# SCB_XTR.net
KiCad netlist of a schematic drawn in Altium Designer
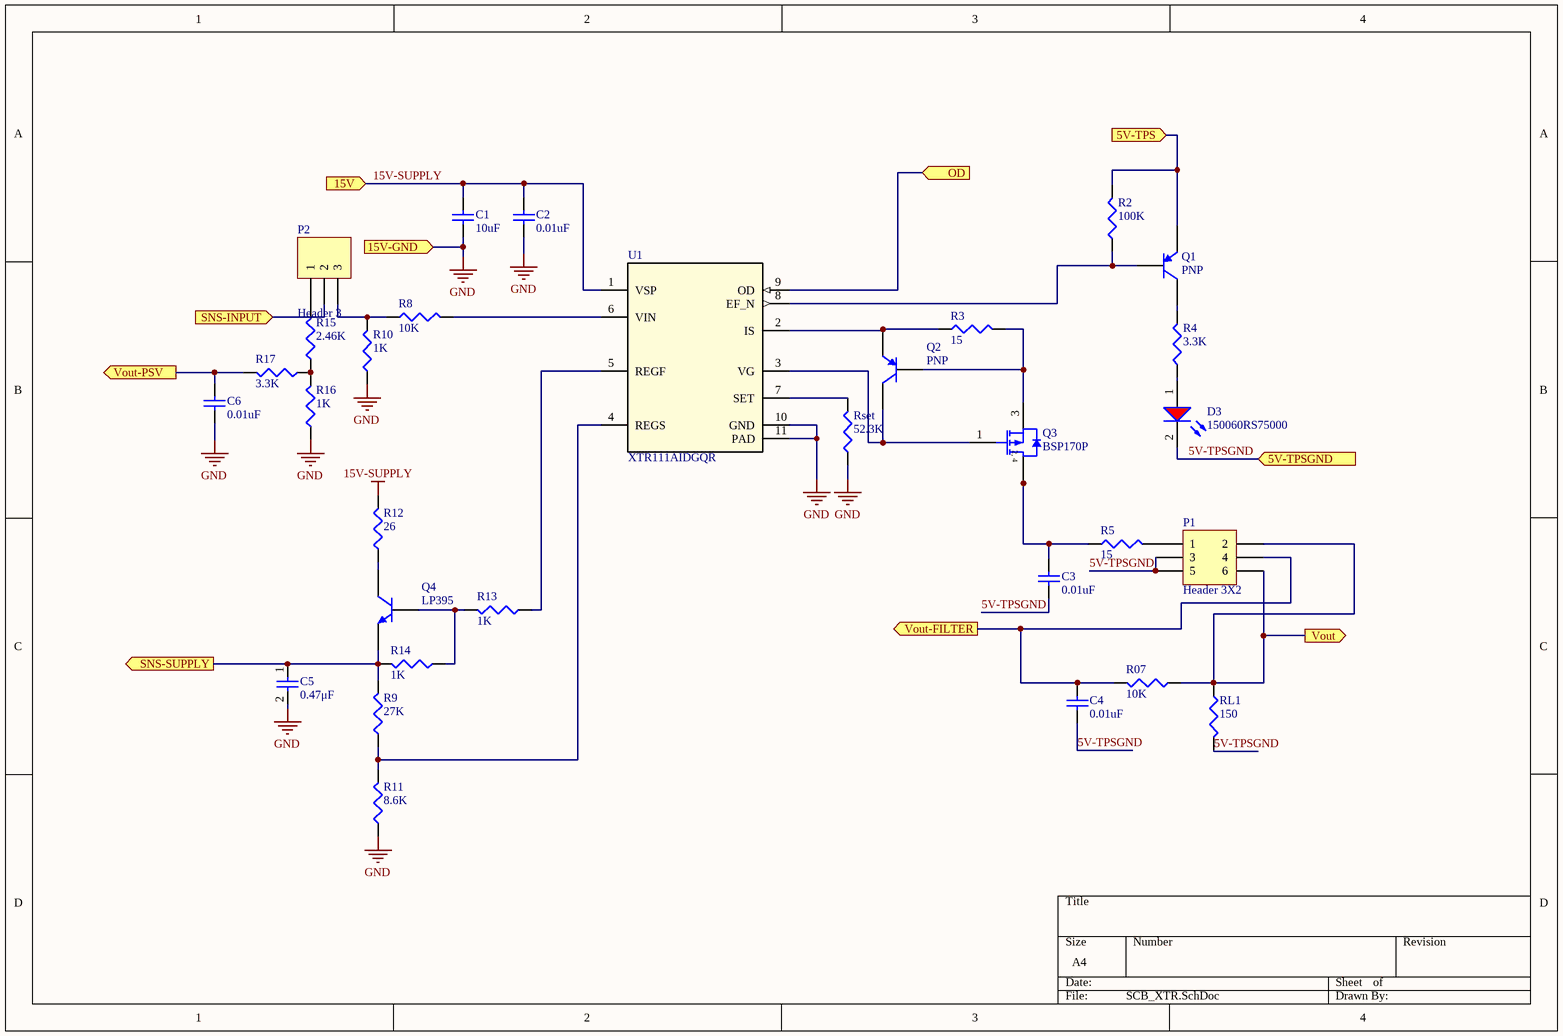
[diagram p0: SCB_XTR.SchDoc]

(export (version "E")
  (design (tool "Eeschema 10.0.6"))
  (components
    (comp (ref "C1")
      (value "10uF")
      (footprint "RAD-0.3")
      (description "Capacitor")
      (fields (field (name "PUBLISHER") "Altium Limited"))
      (libsource (lib "Miscellaneous Devices") (part "Cap"))
    )
    (comp (ref "C2")
      (value "0.01uF")
      (footprint "1608[0603]")
      (description "Capacitor (Semiconductor SIM Model)")
      (fields (field (name "PUBLISHER") "Altium Limited"))
      (libsource (lib "Miscellaneous Devices") (part "Cap Semi"))
    )
    (comp (ref "C3")
      (value "0.01uF")
      (footprint "1608[0603]")
      (description "Capacitor (Semiconductor SIM Model)")
      (fields (field (name "PUBLISHER") "Altium Limited"))
      (libsource (lib "Miscellaneous Devices") (part "Cap Semi"))
    )
    (comp (ref "C4")
      (value "0.01uF")
      (footprint "1608[0603]")
      (description "Capacitor (Semiconductor SIM Model)")
      (fields (field (name "PUBLISHER") "Altium Limited"))
      (libsource (lib "Miscellaneous Devices") (part "Cap Semi"))
    )
    (comp (ref "C5")
      (value "0.47μF")
      (footprint "WCAP-CSGP 0805, H=1.25mm")
      (description "CAP CER 1UF 50V 10% X5R 0805")
      (fields
        (field (name "MANUFACTURER") "TDK")
        (field (name "PARTNO") "CGA4J3X5R1H105K125AB")
        (field (name "CREATED BY") "Saurabh")
      )
      (libsource (lib "WCAP-CSGP_rev15b") (part "WCAP-CSGP 0805, 885012207026"))
    )
    (comp (ref "C6")
      (value "0.01uF")
      (footprint "1608[0603]")
      (description "Capacitor (Semiconductor SIM Model)")
      (fields (field (name "PUBLISHER") "Altium Limited"))
      (libsource (lib "Miscellaneous Devices") (part "Cap Semi"))
    )
    (comp (ref "D3")
      (value "150060RS75000")
      (footprint "LED_0603_Red")
      (description "SMD mono-color Chip LED, WL-SMCW, Red")
      (fields
        (field (name "MANUFACTURER") "W黵th Elektronik eiSos GmbH")
        (field (name "CREATED BY") "Christin Otto")
      )
      (libsource (lib "WL-SMCW_rev15b") (part "WL-SMCW 0603  150060RS75000"))
    )
    (comp (ref "P1")
      (value "Header 3X2")
      (footprint "HDR2X3")
      (description "Header, 3-Pin, Dual row")
      (fields (field (name "PUBLISHER") "Altium Limited"))
      (libsource (lib "Miscellaneous Connectors") (part "Header 3X2"))
    )
    (comp (ref "P2")
      (value "Header 3")
      (footprint "HDR1X3")
      (description "Header, 3-Pin")
      (fields (field (name "PUBLISHER") "Altium Limited"))
      (libsource (lib "Miscellaneous Connectors") (part "Header 3"))
    )
    (comp (ref "Q1")
      (value "PNP")
      (footprint "SOT-23B_N")
      (description "PNP Bipolar Transistor")
      (fields (field (name "PUBLISHER") "Altium Limited"))
      (libsource (lib "Miscellaneous Devices") (part "PNP"))
    )
    (comp (ref "Q2")
      (value "PNP")
      (footprint "SOT-23B_N")
      (description "PNP Bipolar Transistor")
      (fields (field (name "PUBLISHER") "Altium Limited"))
      (libsource (lib "Miscellaneous Devices") (part "PNP"))
    )
    (comp (ref "Q3")
      (value "BSP170P")
      (footprint "INF-PG-SOT223_SC-73_M")
      (fields (field (name "MANUFACTURER") "Infineon"))
      (libsource (lib "BSP170P") (part "BSP170P"))
    )
    (comp (ref "Q4")
      (value "LP395")
      (footprint "TO-92A")
      (description "NPN General Purpose Amplifier")
      (fields (field (name "PUBLISHER") "Altium Limited"))
      (libsource (lib "Miscellaneous Devices") (part "2N3904"))
    )
    (comp (ref "R2")
      (value "100K")
      (footprint "J1-0603")
      (description "Resistor")
      (fields (field (name "PUBLISHER") "Altium Limited"))
      (libsource (lib "Miscellaneous Devices") (part "Res3"))
    )
    (comp (ref "R3")
      (value "15")
      (footprint "J1-0603")
      (description "Resistor")
      (fields (field (name "PUBLISHER") "Altium Limited"))
      (libsource (lib "Miscellaneous Devices") (part "Res3"))
    )
    (comp (ref "R4")
      (value "3.3K")
      (footprint "J1-0603")
      (description "Resistor")
      (fields (field (name "PUBLISHER") "Altium Limited"))
      (libsource (lib "Miscellaneous Devices") (part "Res3"))
    )
    (comp (ref "R5")
      (value "15")
      (footprint "J1-0603")
      (description "Resistor")
      (fields (field (name "PUBLISHER") "Altium Limited"))
      (libsource (lib "Miscellaneous Devices") (part "Res3"))
    )
    (comp (ref "R07")
      (value "10K")
      (footprint "J1-0603")
      (description "Resistor")
      (fields (field (name "PUBLISHER") "Altium Limited"))
      (libsource (lib "Miscellaneous Devices") (part "Res3"))
    )
    (comp (ref "R8")
      (value "10K")
      (footprint "J1-0603")
      (description "Resistor")
      (fields (field (name "PUBLISHER") "Altium Limited"))
      (libsource (lib "Miscellaneous Devices") (part "Res3"))
    )
    (comp (ref "R9")
      (value "27K")
      (footprint "J1-0603")
      (description "Resistor")
      (fields (field (name "PUBLISHER") "Altium Limited"))
      (libsource (lib "Miscellaneous Devices") (part "Res3"))
    )
    (comp (ref "R10")
      (value "1K")
      (footprint "J1-0603")
      (description "Resistor")
      (fields (field (name "PUBLISHER") "Altium Limited"))
      (libsource (lib "Miscellaneous Devices") (part "Res3"))
    )
    (comp (ref "R11")
      (value "8.6K")
      (footprint "J1-0603")
      (description "Resistor")
      (fields (field (name "PUBLISHER") "Altium Limited"))
      (libsource (lib "Miscellaneous Devices") (part "Res3"))
    )
    (comp (ref "R12")
      (value "26")
      (footprint "J1-0603")
      (description "Resistor")
      (fields (field (name "PUBLISHER") "Altium Limited"))
      (libsource (lib "Miscellaneous Devices") (part "Res3"))
    )
    (comp (ref "R13")
      (value "1K")
      (footprint "J1-0603")
      (description "Resistor")
      (fields (field (name "PUBLISHER") "Altium Limited"))
      (libsource (lib "Miscellaneous Devices") (part "Res3"))
    )
    (comp (ref "R14")
      (value "1K")
      (footprint "J1-0603")
      (description "Resistor")
      (fields (field (name "PUBLISHER") "Altium Limited"))
      (libsource (lib "Miscellaneous Devices") (part "Res3"))
    )
    (comp (ref "R15")
      (value "2.46K")
      (footprint "J1-0603")
      (description "Resistor")
      (fields (field (name "PUBLISHER") "Altium Limited"))
      (libsource (lib "Miscellaneous Devices") (part "Res3"))
    )
    (comp (ref "R16")
      (value "1K")
      (footprint "J1-0603")
      (description "Resistor")
      (fields (field (name "PUBLISHER") "Altium Limited"))
      (libsource (lib "Miscellaneous Devices") (part "Res3"))
    )
    (comp (ref "R17")
      (value "3.3K")
      (footprint "J1-0603")
      (description "Resistor")
      (fields (field (name "PUBLISHER") "Altium Limited"))
      (libsource (lib "Miscellaneous Devices") (part "Res3"))
    )
    (comp (ref "RL1")
      (value "150")
      (footprint "J1-0603")
      (description "Resistor")
      (fields (field (name "PUBLISHER") "Altium Limited"))
      (libsource (lib "Miscellaneous Devices") (part "Res3"))
    )
    (comp (ref "Rset")
      (value "52.3K")
      (footprint "RESC2012M")
      (description "Resistor")
      (fields (field (name "PUBLISHER") "Altium Limited"))
      (libsource (lib "Miscellaneous Devices") (part "Res3"))
    )
    (comp (ref "U1")
      (value "XTR111AIDGQR")
      (footprint "DGQ0010D_NV_N")
      (description "Imported")
      (fields (field (name "PARTNUMBER") "XTR111AIDGQT") (field (name "MANUFACTURER") "Texas Instruments"))
      (libsource (lib "2016-09-29_20-01-59") (part "XTR111AIDGQR"))
    )
  )
  (nets
    (net (code "1") (name "/5V-TPS") (class "Default")
      (node (ref "Q1") (pin "3") (pinfunction "E_3") (pintype "passive"))
      (node (ref "R2") (pin "2") (pinfunction "2_2") (pintype "passive"))
    )
    (net (code "2") (name "/5V-TPSGND") (class "Default")
      (node (ref "C3") (pin "1") (pinfunction "1_1") (pintype "passive"))
      (node (ref "C4") (pin "1") (pinfunction "1_1") (pintype "passive"))
      (node (ref "D3") (pin "2") (pinfunction "C_2") (pintype "passive"))
      (node (ref "P1") (pin "3") (pinfunction "3_3") (pintype "passive"))
      (node (ref "P1") (pin "5") (pinfunction "5_5") (pintype "passive"))
      (node (ref "RL1") (pin "2") (pinfunction "2_2") (pintype "passive"))
    )
    (net (code "3") (name "/OD") (class "Default")
      (node (ref "U1") (pin "9") (pinfunction "OD_9") (pintype "input"))
    )
    (net (code "4") (name "/SNS-INPUT") (class "Default")
      (node (ref "P2") (pin "2") (pinfunction "2_2") (pintype "passive"))
    )
    (net (code "5") (name "/SNS-SUPPLY") (class "Default")
      (node (ref "C5") (pin "1") (pinfunction "1_1") (pintype "passive"))
      (node (ref "Q4") (pin "1") (pinfunction "E_1") (pintype "passive"))
      (node (ref "R14") (pin "2") (pinfunction "2_2") (pintype "passive"))
      (node (ref "R9") (pin "2") (pinfunction "2_2") (pintype "passive"))
    )
    (net (code "6") (name "/Vout") (class "Default")
      (node (ref "P1") (pin "2") (pinfunction "2_2") (pintype "passive"))
      (node (ref "P1") (pin "6") (pinfunction "6_6") (pintype "passive"))
      (node (ref "R07") (pin "1") (pinfunction "1_1") (pintype "passive"))
      (node (ref "RL1") (pin "1") (pinfunction "1_1") (pintype "passive"))
    )
    (net (code "7") (name "/Vout-FILTER") (class "Default")
      (node (ref "C4") (pin "2") (pinfunction "2_2") (pintype "passive"))
      (node (ref "P1") (pin "4") (pinfunction "4_4") (pintype "passive"))
      (node (ref "R07") (pin "2") (pinfunction "2_2") (pintype "passive"))
    )
    (net (code "8") (name "/Vout-PSV") (class "Default")
      (node (ref "C6") (pin "2") (pinfunction "2_2") (pintype "passive"))
      (node (ref "R17") (pin "2") (pinfunction "2_2") (pintype "passive"))
    )
    (net (code "9") (name "15V-SUPPLY") (class "Default")
      (node (ref "C1") (pin "2") (pinfunction "2_2") (pintype "passive"))
      (node (ref "C2") (pin "2") (pinfunction "2_2") (pintype "passive"))
      (node (ref "R12") (pin "2") (pinfunction "2_2") (pintype "passive"))
      (node (ref "U1") (pin "1") (pinfunction "VSP_1") (pintype "power_in"))
    )
    (net (code "10") (name "GND") (class "Default")
      (node (ref "C1") (pin "1") (pinfunction "1_1") (pintype "passive"))
      (node (ref "C2") (pin "1") (pinfunction "1_1") (pintype "passive"))
      (node (ref "C5") (pin "2") (pinfunction "2_2") (pintype "passive"))
      (node (ref "C6") (pin "1") (pinfunction "1_1") (pintype "passive"))
      (node (ref "R10") (pin "1") (pinfunction "1_1") (pintype "passive"))
      (node (ref "R11") (pin "1") (pinfunction "1_1") (pintype "passive"))
      (node (ref "R16") (pin "1") (pinfunction "1_1") (pintype "passive"))
      (node (ref "Rset") (pin "1") (pinfunction "1_1") (pintype "passive"))
      (node (ref "U1") (pin "10") (pinfunction "GND_10") (pintype "power_in"))
      (node (ref "U1") (pin "11") (pinfunction "PAD_11") (pintype "power_in"))
    )
    (net (code "11") (name "Net-(C3-Pad2)") (class "Default")
      (node (ref "C3") (pin "2") (pinfunction "2_2") (pintype "passive"))
      (node (ref "Q3") (pin "2") (pinfunction "DRAIN_2") (pintype "passive"))
      (node (ref "Q3") (pin "4") (pinfunction "DRAIN_4") (pintype "passive"))
      (node (ref "R5") (pin "1") (pinfunction "1_1") (pintype "passive"))
    )
    (net (code "12") (name "Net-(D3-A)") (class "Default")
      (node (ref "D3") (pin "1") (pinfunction "A_1") (pintype "passive"))
      (node (ref "R4") (pin "1") (pinfunction "1_1") (pintype "passive"))
    )
    (net (code "13") (name "Net-(P1-Pad1)") (class "Default")
      (node (ref "P1") (pin "1") (pinfunction "1_1") (pintype "passive"))
      (node (ref "R5") (pin "2") (pinfunction "2_2") (pintype "passive"))
    )
    (net (code "14") (name "Net-(P2-Pad1)") (class "Default")
      (node (ref "P2") (pin "1") (pinfunction "1_1") (pintype "passive"))
      (node (ref "R15") (pin "2") (pinfunction "2_2") (pintype "passive"))
    )
    (net (code "15") (name "Net-(P2-Pad3)") (class "Default")
      (node (ref "P2") (pin "3") (pinfunction "3_3") (pintype "passive"))
      (node (ref "R10") (pin "2") (pinfunction "2_2") (pintype "passive"))
      (node (ref "R8") (pin "1") (pinfunction "1_1") (pintype "passive"))
    )
    (net (code "16") (name "Net-(Q1-B)") (class "Default")
      (node (ref "Q1") (pin "2") (pinfunction "B_2") (pintype "passive"))
      (node (ref "R2") (pin "1") (pinfunction "1_1") (pintype "passive"))
      (node (ref "U1") (pin "8") (pinfunction "EF_N_8") (pintype "output"))
    )
    (net (code "17") (name "Net-(Q1-C)") (class "Default")
      (node (ref "Q1") (pin "1") (pinfunction "C_1") (pintype "passive"))
      (node (ref "R4") (pin "2") (pinfunction "2_2") (pintype "passive"))
    )
    (net (code "18") (name "Net-(Q2-B)") (class "Default")
      (node (ref "Q2") (pin "2") (pinfunction "B_2") (pintype "passive"))
      (node (ref "Q3") (pin "3") (pinfunction "SOURCE_3") (pintype "passive"))
      (node (ref "R3") (pin "2") (pinfunction "2_2") (pintype "passive"))
    )
    (net (code "19") (name "Net-(Q2-C)") (class "Default")
      (node (ref "Q2") (pin "1") (pinfunction "C_1") (pintype "passive"))
      (node (ref "Q3") (pin "1") (pinfunction "GATE_1") (pintype "passive"))
      (node (ref "U1") (pin "3") (pinfunction "VG_3") (pintype "passive"))
    )
    (net (code "20") (name "Net-(Q2-E)") (class "Default")
      (node (ref "Q2") (pin "3") (pinfunction "E_3") (pintype "passive"))
      (node (ref "R3") (pin "1") (pinfunction "1_1") (pintype "passive"))
      (node (ref "U1") (pin "2") (pinfunction "IS_2") (pintype "passive"))
    )
    (net (code "21") (name "Net-(Q4-B)") (class "Default")
      (node (ref "Q4") (pin "2") (pinfunction "B_2") (pintype "passive"))
      (node (ref "R13") (pin "2") (pinfunction "2_2") (pintype "passive"))
      (node (ref "R14") (pin "1") (pinfunction "1_1") (pintype "passive"))
    )
    (net (code "22") (name "Net-(Q4-C)") (class "Default")
      (node (ref "Q4") (pin "3") (pinfunction "C_3") (pintype "passive"))
      (node (ref "R12") (pin "1") (pinfunction "1_1") (pintype "passive"))
    )
    (net (code "23") (name "Net-(R15-Pad1)") (class "Default")
      (node (ref "R15") (pin "1") (pinfunction "1_1") (pintype "passive"))
      (node (ref "R16") (pin "2") (pinfunction "2_2") (pintype "passive"))
      (node (ref "R17") (pin "1") (pinfunction "1_1") (pintype "passive"))
    )
    (net (code "24") (name "Net-(U1-REGF)") (class "Default")
      (node (ref "R13") (pin "1") (pinfunction "1_1") (pintype "passive"))
      (node (ref "U1") (pin "5") (pinfunction "REGF_5") (pintype "passive"))
    )
    (net (code "25") (name "Net-(U1-REGS)") (class "Default")
      (node (ref "R11") (pin "2") (pinfunction "2_2") (pintype "passive"))
      (node (ref "R9") (pin "1") (pinfunction "1_1") (pintype "passive"))
      (node (ref "U1") (pin "4") (pinfunction "REGS_4") (pintype "passive"))
    )
    (net (code "26") (name "Net-(U1-SET)") (class "Default")
      (node (ref "Rset") (pin "2") (pinfunction "2_2") (pintype "passive"))
      (node (ref "U1") (pin "7") (pinfunction "SET_7") (pintype "passive"))
    )
    (net (code "27") (name "Net-(U1-VIN)") (class "Default")
      (node (ref "R8") (pin "2") (pinfunction "2_2") (pintype "passive"))
      (node (ref "U1") (pin "6") (pinfunction "VIN_6") (pintype "power_in"))
    )
  )
)
